# ECU_Sheet5.net
KiCad netlist of a schematic drawn in Altium Designer
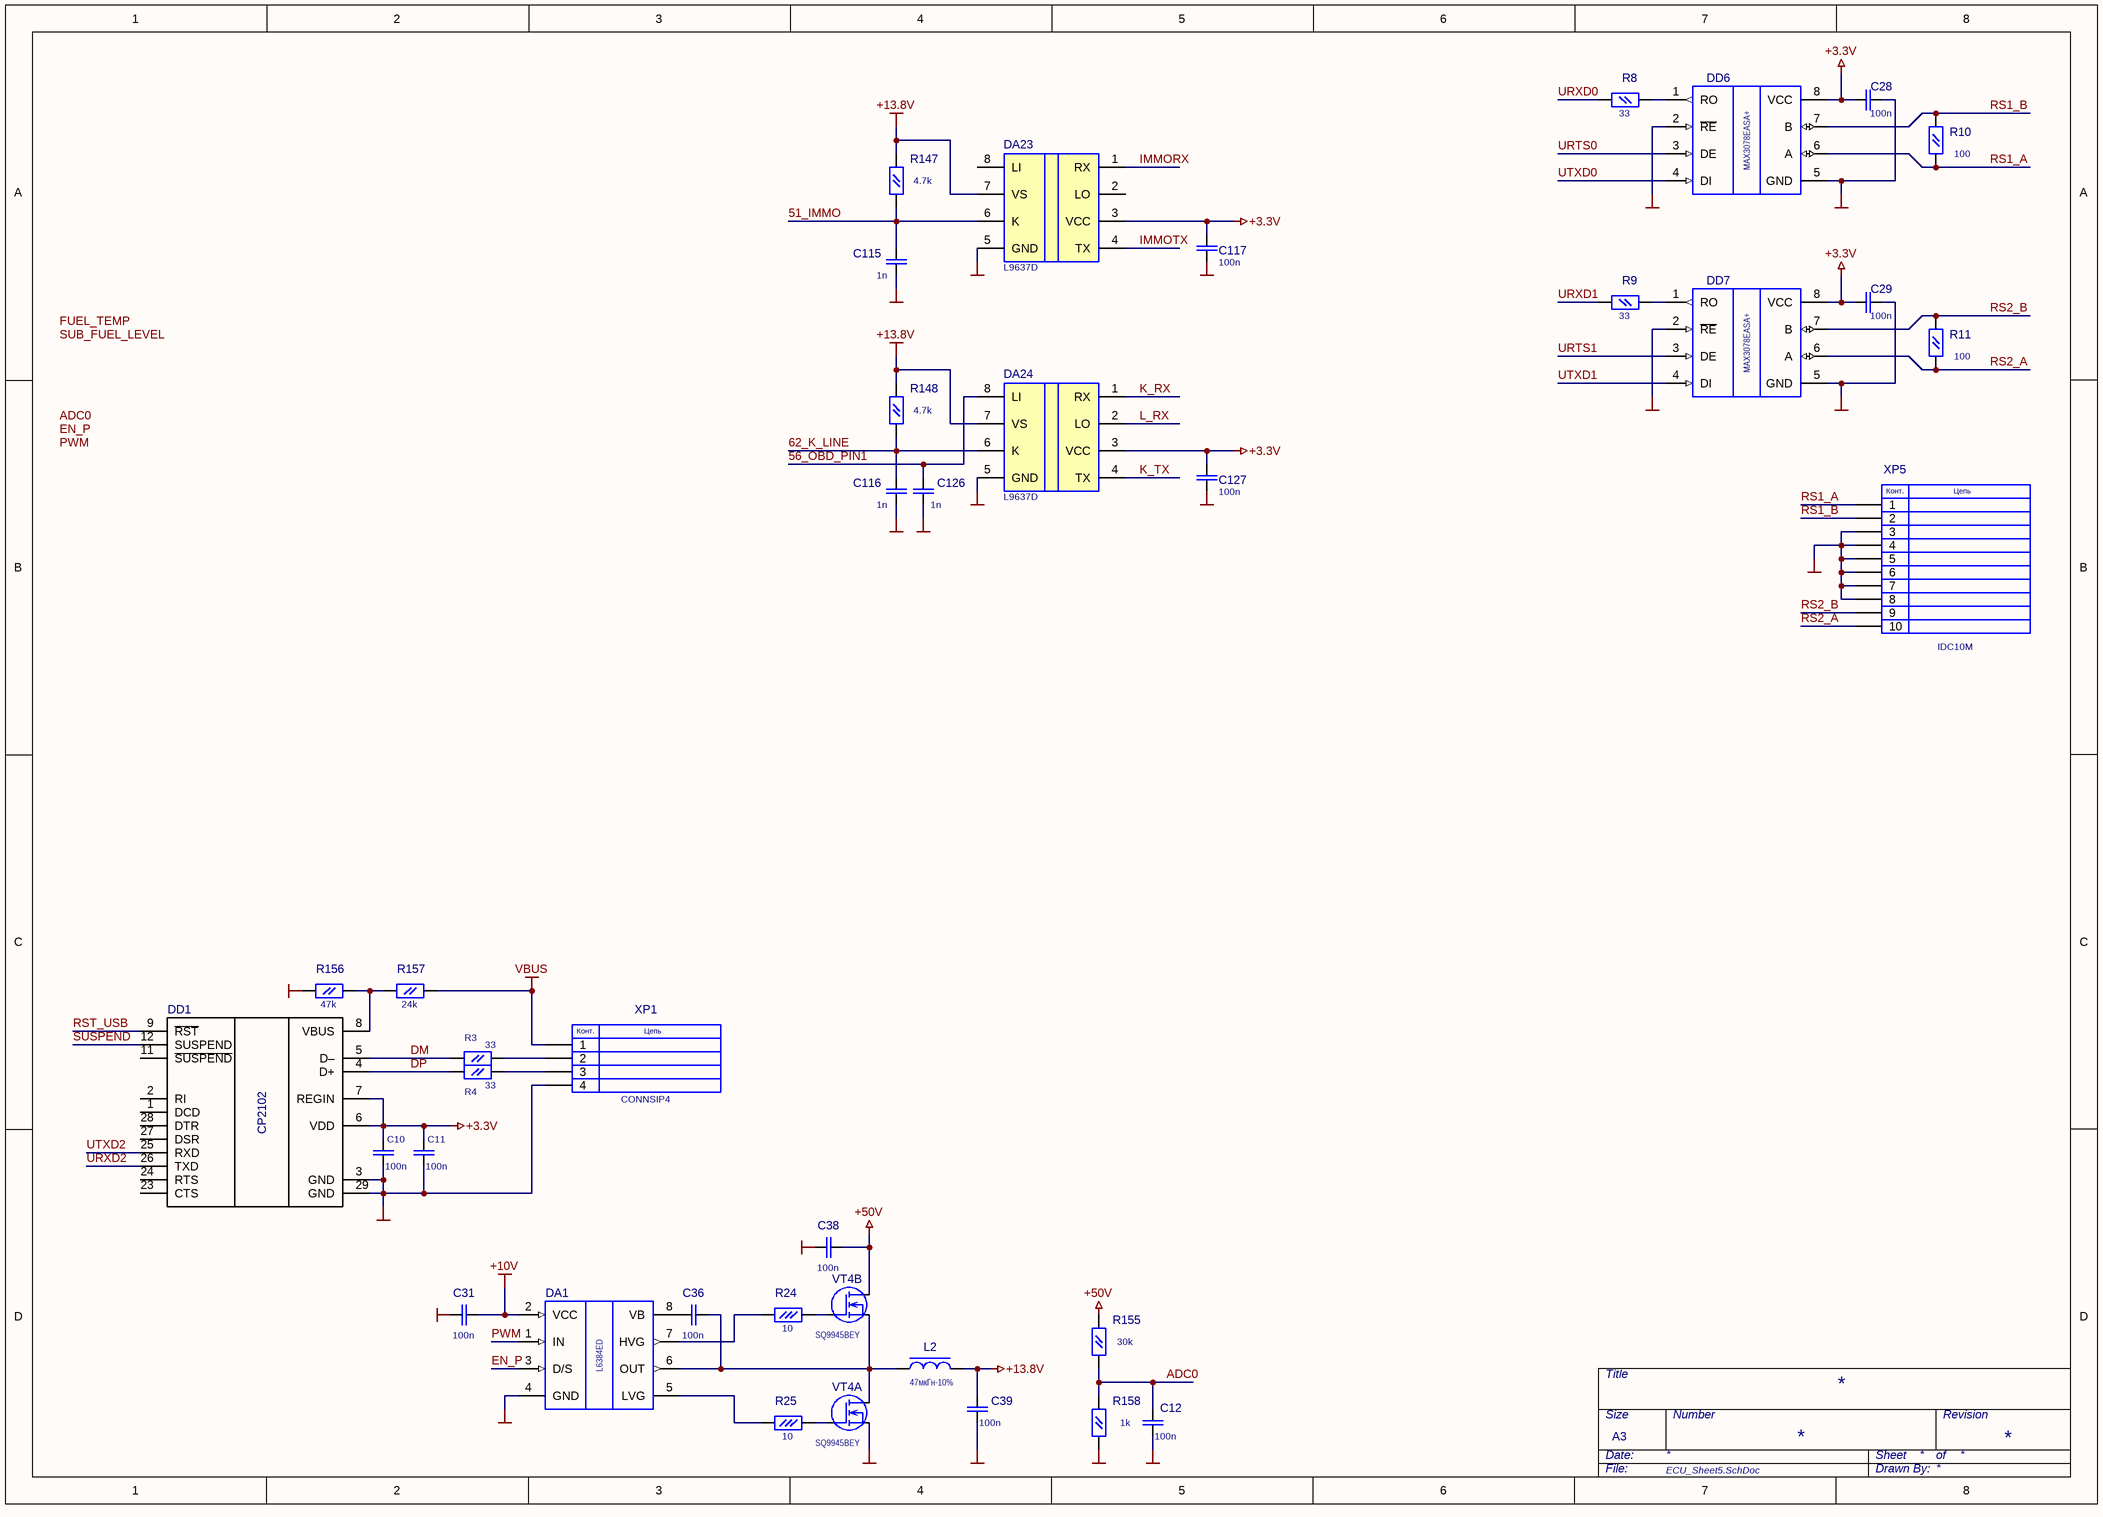
[diagram p0: ECU_Sheet5.SchDoc]

(export (version "E")
  (design (tool "Eeschema 10.0.6"))
  (components
    (comp (ref "C10")
      (value "100n")
      (footprint "C0603L")
      (description "C0603")
      (fields (field (name "Comment") "CSMD"))
      (libsource (lib "L1") (part "CSMD"))
    )
    (comp (ref "C11")
      (value "100n")
      (footprint "C0603L")
      (description "C0603")
      (fields (field (name "Comment") "CSMD"))
      (libsource (lib "L1") (part "CSMD"))
    )
    (comp (ref "C12")
      (value "100n")
      (footprint "C0805L")
      (description "C0603")
      (fields (field (name "Comment") "0.1мкФ-25В-X8R-10%"))
      (libsource (lib "L1") (part "CSMD"))
    )
    (comp (ref "C28")
      (value "100n")
      (footprint "C0805L")
      (description "C0603")
      (fields (field (name "Comment") "0.1мкФ-50В-X8R-10%"))
      (libsource (lib "L1") (part "CSMD"))
    )
    (comp (ref "C29")
      (value "100n")
      (footprint "C0805L")
      (description "C0603")
      (fields (field (name "Comment") "0.1мкФ-50В-X8R-10%"))
      (libsource (lib "L1") (part "CSMD"))
    )
    (comp (ref "C31")
      (value "100n")
      (footprint "C0805L")
      (description "C0603")
      (fields (field (name "Comment") "CSMD"))
      (libsource (lib "L1") (part "CSMD"))
    )
    (comp (ref "C36")
      (value "100n")
      (footprint "C0805L")
      (description "C0603")
      (fields (field (name "Comment") "CSMD"))
      (libsource (lib "L1") (part "CSMD"))
    )
    (comp (ref "C38")
      (value "100n")
      (footprint "C0805L")
      (description "C0603")
      (fields (field (name "Comment") "CSMD"))
      (libsource (lib "L1") (part "CSMD"))
    )
    (comp (ref "C39")
      (value "100n")
      (footprint "C0805L")
      (description "C0603")
      (fields (field (name "Comment") "0.1мкФ-25В-X8R-10%"))
      (libsource (lib "L1") (part "CSMD"))
    )
    (comp (ref "C115")
      (value "1n")
      (footprint "C0805L")
      (description "C0603")
      (fields (field (name "Comment") "CSMD"))
      (libsource (lib "L1") (part "CSMD"))
    )
    (comp (ref "C116")
      (value "1n")
      (footprint "C0805L")
      (description "C0603")
      (fields (field (name "Comment") "CSMD"))
      (libsource (lib "L1") (part "CSMD"))
    )
    (comp (ref "C117")
      (value "100n")
      (footprint "C0805L")
      (description "C0603")
      (fields (field (name "Comment") "1мкФ-25В-X7R-10%"))
      (libsource (lib "L1") (part "CSMD"))
    )
    (comp (ref "C126")
      (value "1n")
      (footprint "C0805L")
      (description "C0603")
      (fields (field (name "Comment") "CSMD"))
      (libsource (lib "L1") (part "CSMD"))
    )
    (comp (ref "C127")
      (value "100n")
      (footprint "C0805L")
      (description "C0603")
      (fields (field (name "Comment") "1мкФ-25В-X7R-10%"))
      (libsource (lib "L1") (part "CSMD"))
    )
    (comp (ref "DA1") (value "L6384ED") (footprint "SOIC8 JEDEC") (libsource (lib "ECULIB") (part "L6384ED")))
    (comp (ref "DA23")
      (value "L9637D")
      (footprint "SOIC8 JEDEC")
      (description "Monolithic bus driver with ISO 9141 interface")
      (libsource (lib "L1") (part "L9637"))
    )
    (comp (ref "DA24")
      (value "L9637D")
      (footprint "SOIC8 JEDEC")
      (description "Monolithic bus driver with ISO 9141 interface")
      (libsource (lib "L1") (part "L9637"))
    )
    (comp (ref "DD1") (value "CP2102") (footprint "QFN-28") (libsource (lib "L1") (part "CP2102")))
    (comp (ref "DD6")
      (value "MAX3078EASA+")
      (footprint "SOIC8 JEDEC")
      (description "MAX3078EASA+ или ISL3179EFBZ или ADM3078EYRZ")
      (libsource (lib "RL1") (part "MAX3088ESA"))
    )
    (comp (ref "DD7")
      (value "MAX3078EASA+")
      (footprint "SOIC8 JEDEC")
      (description "MAX3078EASA+ или ISL3179EFBZ или ADM3078EYRZ")
      (libsource (lib "RL1") (part "MAX3088ESA"))
    )
    (comp (ref "L2") (value "47мкГн-10%") (footprint "L_SDR0604") (libsource (lib "*") (part "DROSSEL3")))
    (comp (ref "R3")
      (value "33")
      (footprint "R0603L")
      (description "R0805")
      (fields (field (name "Comment") "RSMD"))
      (libsource (lib "L1") (part "RSMD"))
    )
    (comp (ref "R4")
      (value "33")
      (footprint "R0603L")
      (description "R0805")
      (fields (field (name "Comment") "RSMD"))
      (libsource (lib "L1") (part "RSMD"))
    )
    (comp (ref "R8")
      (value "33")
      (footprint "R0603L")
      (description "R0805")
      (fields (field (name "Comment") "33-5%"))
      (libsource (lib "L1") (part "RSMD"))
    )
    (comp (ref "R9")
      (value "33")
      (footprint "R0603L")
      (description "R0805")
      (fields (field (name "Comment") "33-5%"))
      (libsource (lib "L1") (part "RSMD"))
    )
    (comp (ref "R10")
      (value "100")
      (footprint "R0805L")
      (description "R0805")
      (fields (field (name "Comment") "100-5%"))
      (libsource (lib "L1") (part "RSMD"))
    )
    (comp (ref "R11")
      (value "100")
      (footprint "R0805L")
      (description "R0805")
      (fields (field (name "Comment") "100-5%"))
      (libsource (lib "L1") (part "RSMD"))
    )
    (comp (ref "R24")
      (value "10")
      (footprint "R0603L")
      (description "R0805")
      (fields (field (name "Comment") "100-5%"))
      (libsource (lib "") (part "RSMD_1"))
    )
    (comp (ref "R25")
      (value "10")
      (footprint "R0603L")
      (description "R0805")
      (fields (field (name "Comment") "100-5%"))
      (libsource (lib "") (part "RSMD_1"))
    )
    (comp (ref "R147")
      (value "4.7k")
      (footprint "R0805L")
      (description "R0805")
      (fields (field (name "Comment") "RSMD"))
      (libsource (lib "L1") (part "RSMD"))
    )
    (comp (ref "R148")
      (value "4.7k")
      (footprint "R0805L")
      (description "R0805")
      (fields (field (name "Comment") "RSMD"))
      (libsource (lib "L1") (part "RSMD"))
    )
    (comp (ref "R155")
      (value "30k")
      (footprint "R0805L")
      (description "R0805")
      (fields (field (name "Comment") "RSMD"))
      (libsource (lib "L1") (part "RSMD"))
    )
    (comp (ref "R156")
      (value "47k")
      (footprint "R0805L")
      (description "R0805")
      (fields (field (name "Comment") "RSMD"))
      (libsource (lib "L1") (part "RSMD"))
    )
    (comp (ref "R157")
      (value "24k")
      (footprint "R0805L")
      (description "R0805")
      (fields (field (name "Comment") "RSMD"))
      (libsource (lib "L1") (part "RSMD"))
    )
    (comp (ref "R158")
      (value "1k")
      (footprint "R0805L")
      (description "R0805")
      (fields (field (name "Comment") "RSMD"))
      (libsource (lib "L1") (part "RSMD"))
    )
    (comp (ref "VT4")
      (value "SQ9945BEY")
      (footprint "SOIC8 DBL FET")
      (libsource (lib "L1") (part "SQ9945BEY"))
    )
    (comp (ref "XP1") (value "CONNSIP4") (footprint "SIP4") (libsource (lib "RL1") (part "CONNSIP4")))
    (comp (ref "XP5") (value "IDC10M") (footprint "IDC10M") (libsource (lib "RL1") (part "IDC10M")))
  )
  (nets
    (net (code "1") (name "+3.3V") (class "Default")
      (node (ref "C10") (pin "2") (pintype "passive"))
      (node (ref "C11") (pin "2") (pintype "passive"))
      (node (ref "C117") (pin "2") (pintype "passive"))
      (node (ref "C127") (pin "2") (pintype "passive"))
      (node (ref "C28") (pin "1") (pintype "passive"))
      (node (ref "C29") (pin "1") (pintype "passive"))
      (node (ref "DA23") (pin "3") (pinfunction "VCC_3") (pintype "passive"))
      (node (ref "DA24") (pin "3") (pinfunction "VCC_3") (pintype "passive"))
      (node (ref "DD1") (pin "6") (pinfunction "VDD_6") (pintype "passive"))
      (node (ref "DD1") (pin "7") (pinfunction "REGIN_7") (pintype "passive"))
      (node (ref "DD6") (pin "8") (pinfunction "VCC_8") (pintype "power_in"))
      (node (ref "DD7") (pin "8") (pinfunction "VCC_8") (pintype "power_in"))
    )
    (net (code "2") (name "+10V") (class "Default")
      (node (ref "C31") (pin "1") (pintype "passive"))
      (node (ref "DA1") (pin "2") (pinfunction "VCC_2") (pintype "input"))
    )
    (net (code "3") (name "+13.8V") (class "Default")
      (node (ref "C39") (pin "1") (pintype "passive"))
      (node (ref "DA23") (pin "7") (pinfunction "VS_7") (pintype "passive"))
      (node (ref "DA24") (pin "7") (pinfunction "VS_7") (pintype "passive"))
      (node (ref "L2") (pin "1") (pinfunction "1_1") (pintype "passive"))
      (node (ref "R147") (pin "2") (pinfunction "Pin2_2") (pintype "passive"))
      (node (ref "R148") (pin "2") (pinfunction "Pin2_2") (pintype "passive"))
    )
    (net (code "4") (name "+50V") (class "Default")
      (node (ref "C38") (pin "1") (pintype "passive"))
      (node (ref "R155") (pin "2") (pinfunction "Pin2_2") (pintype "passive"))
      (node (ref "VT4") (pin "5") (pintype "passive"))
    )
    (net (code "5") (name "/51_IMMO") (class "Default")
      (node (ref "C115") (pin "1") (pintype "passive"))
      (node (ref "DA23") (pin "6") (pinfunction "K_6") (pintype "passive"))
      (node (ref "R147") (pin "1") (pinfunction "Pin1_1") (pintype "passive"))
    )
    (net (code "6") (name "/56_OBD_PIN1") (class "Default")
      (node (ref "C126") (pin "1") (pintype "passive"))
      (node (ref "DA24") (pin "8") (pinfunction "LI_8") (pintype "passive"))
    )
    (net (code "7") (name "/62_K_LINE") (class "Default")
      (node (ref "C116") (pin "1") (pintype "passive"))
      (node (ref "DA24") (pin "6") (pinfunction "K_6") (pintype "passive"))
      (node (ref "R148") (pin "1") (pinfunction "Pin1_1") (pintype "passive"))
    )
    (net (code "8") (name "/ADC0") (class "Default")
      (node (ref "C12") (pin "2") (pintype "passive"))
      (node (ref "R155") (pin "1") (pinfunction "Pin1_1") (pintype "passive"))
      (node (ref "R158") (pin "2") (pinfunction "Pin2_2") (pintype "passive"))
    )
    (net (code "9") (name "/DM") (class "Default")
      (node (ref "DD1") (pin "5") (pinfunction "D_5") (pintype "passive"))
      (node (ref "R3") (pin "1") (pinfunction "Pin1_1") (pintype "passive"))
    )
    (net (code "10") (name "/DP") (class "Default")
      (node (ref "DD1") (pin "4") (pinfunction "D+_4") (pintype "passive"))
      (node (ref "R4") (pin "1") (pinfunction "Pin1_1") (pintype "passive"))
    )
    (net (code "11") (name "/EN_P") (class "Default")
      (node (ref "DA1") (pin "3") (pinfunction "D/S_3") (pintype "input"))
    )
    (net (code "13") (name "/IMMORX") (class "Default")
      (node (ref "DA23") (pin "1") (pinfunction "RX_1") (pintype "passive"))
    )
    (net (code "14") (name "/IMMOTX") (class "Default")
      (node (ref "DA23") (pin "4") (pinfunction "TX_4") (pintype "passive"))
    )
    (net (code "15") (name "/K_RX") (class "Default")
      (node (ref "DA24") (pin "1") (pinfunction "RX_1") (pintype "passive"))
    )
    (net (code "16") (name "/K_TX") (class "Default")
      (node (ref "DA24") (pin "4") (pinfunction "TX_4") (pintype "passive"))
    )
    (net (code "17") (name "/L_RX") (class "Default")
      (node (ref "DA24") (pin "2") (pinfunction "LO_2") (pintype "passive"))
    )
    (net (code "18") (name "/PWM") (class "Default")
      (node (ref "DA1") (pin "1") (pinfunction "IN_1") (pintype "input"))
    )
    (net (code "19") (name "/RS1_A") (class "Default")
      (node (ref "DD6") (pin "6") (pinfunction "A_6") (pintype "bidirectional"))
      (node (ref "R10") (pin "1") (pinfunction "Pin1_1") (pintype "passive"))
      (node (ref "XP5") (pin "1") (pinfunction "1_1") (pintype "passive"))
    )
    (net (code "20") (name "/RS1_B") (class "Default")
      (node (ref "DD6") (pin "7") (pinfunction "B_7") (pintype "bidirectional"))
      (node (ref "R10") (pin "2") (pinfunction "Pin2_2") (pintype "passive"))
      (node (ref "XP5") (pin "2") (pinfunction "2_2") (pintype "passive"))
    )
    (net (code "21") (name "/RS2_A") (class "Default")
      (node (ref "DD7") (pin "6") (pinfunction "A_6") (pintype "bidirectional"))
      (node (ref "R11") (pin "1") (pinfunction "Pin1_1") (pintype "passive"))
      (node (ref "XP5") (pin "10") (pinfunction "10_10") (pintype "passive"))
    )
    (net (code "22") (name "/RS2_B") (class "Default")
      (node (ref "DD7") (pin "7") (pinfunction "B_7") (pintype "bidirectional"))
      (node (ref "R11") (pin "2") (pinfunction "Pin2_2") (pintype "passive"))
      (node (ref "XP5") (pin "9") (pinfunction "9_9") (pintype "passive"))
    )
    (net (code "23") (name "/RST_USB") (class "Default")
      (node (ref "DD1") (pin "9") (pinfunction "~{RST}_9") (pintype "passive"))
    )
    (net (code "25") (name "/SUSPEND") (class "Default")
      (node (ref "DD1") (pin "12") (pinfunction "SUSPEND_12") (pintype "passive"))
    )
    (net (code "26") (name "/URTS0") (class "Default")
      (node (ref "DD6") (pin "3") (pinfunction "DE_3") (pintype "input"))
    )
    (net (code "27") (name "/URTS1") (class "Default")
      (node (ref "DD7") (pin "3") (pinfunction "DE_3") (pintype "input"))
    )
    (net (code "28") (name "/URXD0") (class "Default")
      (node (ref "R8") (pin "2") (pinfunction "Pin2_2") (pintype "passive"))
    )
    (net (code "29") (name "/URXD1") (class "Default")
      (node (ref "R9") (pin "2") (pinfunction "Pin2_2") (pintype "passive"))
    )
    (net (code "30") (name "/URXD2") (class "Default")
      (node (ref "DD1") (pin "26") (pinfunction "TXD_26") (pintype "passive"))
    )
    (net (code "31") (name "/UTXD0") (class "Default")
      (node (ref "DD6") (pin "4") (pinfunction "DI_4") (pintype "input"))
    )
    (net (code "32") (name "/UTXD1") (class "Default")
      (node (ref "DD7") (pin "4") (pinfunction "DI_4") (pintype "input"))
    )
    (net (code "33") (name "/UTXD2") (class "Default")
      (node (ref "DD1") (pin "25") (pinfunction "RXD_25") (pintype "passive"))
    )
    (net (code "34") (name "GND") (class "Default")
      (node (ref "C10") (pin "1") (pintype "passive"))
      (node (ref "C11") (pin "1") (pintype "passive"))
      (node (ref "C115") (pin "2") (pintype "passive"))
      (node (ref "C116") (pin "2") (pintype "passive"))
      (node (ref "C117") (pin "1") (pintype "passive"))
      (node (ref "C12") (pin "1") (pintype "passive"))
      (node (ref "C126") (pin "2") (pintype "passive"))
      (node (ref "C127") (pin "1") (pintype "passive"))
      (node (ref "C28") (pin "2") (pintype "passive"))
      (node (ref "C29") (pin "2") (pintype "passive"))
      (node (ref "C31") (pin "2") (pintype "passive"))
      (node (ref "C38") (pin "2") (pintype "passive"))
      (node (ref "C39") (pin "2") (pintype "passive"))
      (node (ref "DA1") (pin "4") (pinfunction "GND_4") (pintype "power_in"))
      (node (ref "DA23") (pin "5") (pinfunction "GND_5") (pintype "passive"))
      (node (ref "DA24") (pin "5") (pinfunction "GND_5") (pintype "passive"))
      (node (ref "DD1") (pin "29") (pinfunction "GND_29") (pintype "passive"))
      (node (ref "DD1") (pin "3") (pinfunction "GND_3") (pintype "passive"))
      (node (ref "DD6") (pin "2") (pinfunction "~{RE}_2") (pintype "input"))
      (node (ref "DD6") (pin "5") (pinfunction "GND_5") (pintype "power_in"))
      (node (ref "DD7") (pin "2") (pinfunction "~{RE}_2") (pintype "input"))
      (node (ref "DD7") (pin "5") (pinfunction "GND_5") (pintype "power_in"))
      (node (ref "R156") (pin "1") (pinfunction "Pin1_1") (pintype "passive"))
      (node (ref "R158") (pin "1") (pinfunction "Pin1_1") (pintype "passive"))
      (node (ref "VT4") (pin "1") (pintype "passive"))
      (node (ref "XP1") (pin "4") (pinfunction "4_4") (pintype "passive"))
      (node (ref "XP5") (pin "3") (pinfunction "3_3") (pintype "passive"))
      (node (ref "XP5") (pin "4") (pinfunction "4_4") (pintype "passive"))
      (node (ref "XP5") (pin "5") (pinfunction "5_5") (pintype "passive"))
      (node (ref "XP5") (pin "6") (pinfunction "6_6") (pintype "passive"))
      (node (ref "XP5") (pin "7") (pinfunction "7_7") (pintype "passive"))
      (node (ref "XP5") (pin "8") (pinfunction "8_8") (pintype "passive"))
    )
    (net (code "35") (name "Net-(DA1-HVG)") (class "Default")
      (node (ref "DA1") (pin "7") (pinfunction "HVG_7") (pintype "output"))
      (node (ref "R24") (pin "2") (pintype "passive"))
    )
    (net (code "36") (name "Net-(DA1-LVG)") (class "Default")
      (node (ref "DA1") (pin "5") (pinfunction "LVG_5") (pintype "power_in"))
      (node (ref "R25") (pin "2") (pintype "passive"))
    )
    (net (code "37") (name "Net-(DA1-OUT)") (class "Default")
      (node (ref "C36") (pin "1") (pintype "passive"))
      (node (ref "DA1") (pin "6") (pinfunction "OUT_6") (pintype "output"))
      (node (ref "L2") (pin "2") (pinfunction "2_2") (pintype "passive"))
      (node (ref "VT4") (pin "3") (pintype "passive"))
      (node (ref "VT4") (pin "6") (pintype "passive"))
    )
    (net (code "38") (name "Net-(DA1-VB)") (class "Default")
      (node (ref "C36") (pin "2") (pintype "passive"))
      (node (ref "DA1") (pin "8") (pinfunction "VB_8") (pintype "power_in"))
    )
    (net (code "39") (name "Net-(DD1-VBUS)") (class "Default")
      (node (ref "DD1") (pin "8") (pinfunction "VBUS_8") (pintype "passive"))
      (node (ref "R156") (pin "2") (pinfunction "Pin2_2") (pintype "passive"))
      (node (ref "R157") (pin "1") (pinfunction "Pin1_1") (pintype "passive"))
    )
    (net (code "40") (name "Net-(DD6-RO)") (class "Default")
      (node (ref "DD6") (pin "1") (pinfunction "RO_1") (pintype "output"))
      (node (ref "R8") (pin "1") (pinfunction "Pin1_1") (pintype "passive"))
    )
    (net (code "41") (name "Net-(DD7-RO)") (class "Default")
      (node (ref "DD7") (pin "1") (pinfunction "RO_1") (pintype "output"))
      (node (ref "R9") (pin "1") (pinfunction "Pin1_1") (pintype "passive"))
    )
    (net (code "42") (name "Net-(R3-Pin2)") (class "Default")
      (node (ref "R3") (pin "2") (pinfunction "Pin2_2") (pintype "passive"))
      (node (ref "XP1") (pin "2") (pinfunction "2_2") (pintype "passive"))
    )
    (net (code "43") (name "Net-(R4-Pin2)") (class "Default")
      (node (ref "R4") (pin "2") (pinfunction "Pin2_2") (pintype "passive"))
      (node (ref "XP1") (pin "3") (pinfunction "3_3") (pintype "passive"))
    )
    (net (code "44") (name "Net-(R24-Pad1)") (class "Default")
      (node (ref "R24") (pin "1") (pintype "passive"))
      (node (ref "VT4") (pin "4") (pintype "passive"))
    )
    (net (code "45") (name "Net-(R25-Pad1)") (class "Default")
      (node (ref "R25") (pin "1") (pintype "passive"))
      (node (ref "VT4") (pin "2") (pintype "passive"))
    )
    (net (code "46") (name "VBUS") (class "Default")
      (node (ref "R157") (pin "2") (pinfunction "Pin2_2") (pintype "passive"))
      (node (ref "XP1") (pin "1") (pinfunction "1_1") (pintype "passive"))
    )
    (net (code "47") (name "unconnected-(DA23-LI-Pad8)") (class "Default")
      (node (ref "DA23") (pin "8") (pinfunction "LI_8") (pintype "passive"))
    )
    (net (code "48") (name "unconnected-(DA23-LO-Pad2)") (class "Default")
      (node (ref "DA23") (pin "2") (pinfunction "LO_2") (pintype "passive"))
    )
    (net (code "49") (name "unconnected-(DD1-CTS-Pad23)") (class "Default")
      (node (ref "DD1") (pin "23") (pinfunction "CTS_23") (pintype "passive"))
    )
    (net (code "50") (name "unconnected-(DD1-DCD-Pad1)") (class "Default")
      (node (ref "DD1") (pin "1") (pinfunction "DCD_1") (pintype "passive"))
    )
    (net (code "51") (name "unconnected-(DD1-DSR-Pad27)") (class "Default")
      (node (ref "DD1") (pin "27") (pinfunction "DSR_27") (pintype "passive"))
    )
    (net (code "52") (name "unconnected-(DD1-DTR-Pad28)") (class "Default")
      (node (ref "DD1") (pin "28") (pinfunction "DTR_28") (pintype "passive"))
    )
    (net (code "53") (name "unconnected-(DD1-NC-Pad10)") (class "Default")
      (node (ref "DD1") (pin "10") (pinfunction "NC_10") (pintype "passive"))
    )
    (net (code "54") (name "unconnected-(DD1-NC-Pad13)") (class "Default")
      (node (ref "DD1") (pin "13") (pinfunction "NC_13") (pintype "passive"))
    )
    (net (code "55") (name "unconnected-(DD1-NC-Pad14)") (class "Default")
      (node (ref "DD1") (pin "14") (pinfunction "NC_14") (pintype "passive"))
    )
    (net (code "56") (name "unconnected-(DD1-NC-Pad15)") (class "Default")
      (node (ref "DD1") (pin "15") (pinfunction "NC_15") (pintype "passive"))
    )
    (net (code "57") (name "unconnected-(DD1-NC-Pad16)") (class "Default")
      (node (ref "DD1") (pin "16") (pinfunction "NC_16") (pintype "passive"))
    )
    (net (code "58") (name "unconnected-(DD1-NC-Pad17)") (class "Default")
      (node (ref "DD1") (pin "17") (pinfunction "NC_17") (pintype "passive"))
    )
    (net (code "59") (name "unconnected-(DD1-NC-Pad18)") (class "Default")
      (node (ref "DD1") (pin "18") (pinfunction "NC_18") (pintype "passive"))
    )
    (net (code "60") (name "unconnected-(DD1-NC-Pad19)") (class "Default")
      (node (ref "DD1") (pin "19") (pinfunction "NC_19") (pintype "passive"))
    )
    (net (code "61") (name "unconnected-(DD1-NC-Pad20)") (class "Default")
      (node (ref "DD1") (pin "20") (pinfunction "NC_20") (pintype "passive"))
    )
    (net (code "62") (name "unconnected-(DD1-NC-Pad21)") (class "Default")
      (node (ref "DD1") (pin "21") (pinfunction "NC_21") (pintype "passive"))
    )
    (net (code "63") (name "unconnected-(DD1-NC-Pad22)") (class "Default")
      (node (ref "DD1") (pin "22") (pinfunction "NC_22") (pintype "passive"))
    )
    (net (code "64") (name "unconnected-(DD1-RI-Pad2)") (class "Default")
      (node (ref "DD1") (pin "2") (pinfunction "RI_2") (pintype "passive"))
    )
    (net (code "65") (name "unconnected-(DD1-RTS-Pad24)") (class "Default")
      (node (ref "DD1") (pin "24") (pinfunction "RTS_24") (pintype "passive"))
    )
    (net (code "66") (name "unconnected-(DD1-~{SUSPEND}-Pad11)") (class "Default")
      (node (ref "DD1") (pin "11") (pinfunction "~{SUSPEND}_11") (pintype "passive"))
    )
  )
)
